# ATSAME51G19A_CAN_BREAKOUT.net
KiCad netlist of a schematic drawn in EAGLE
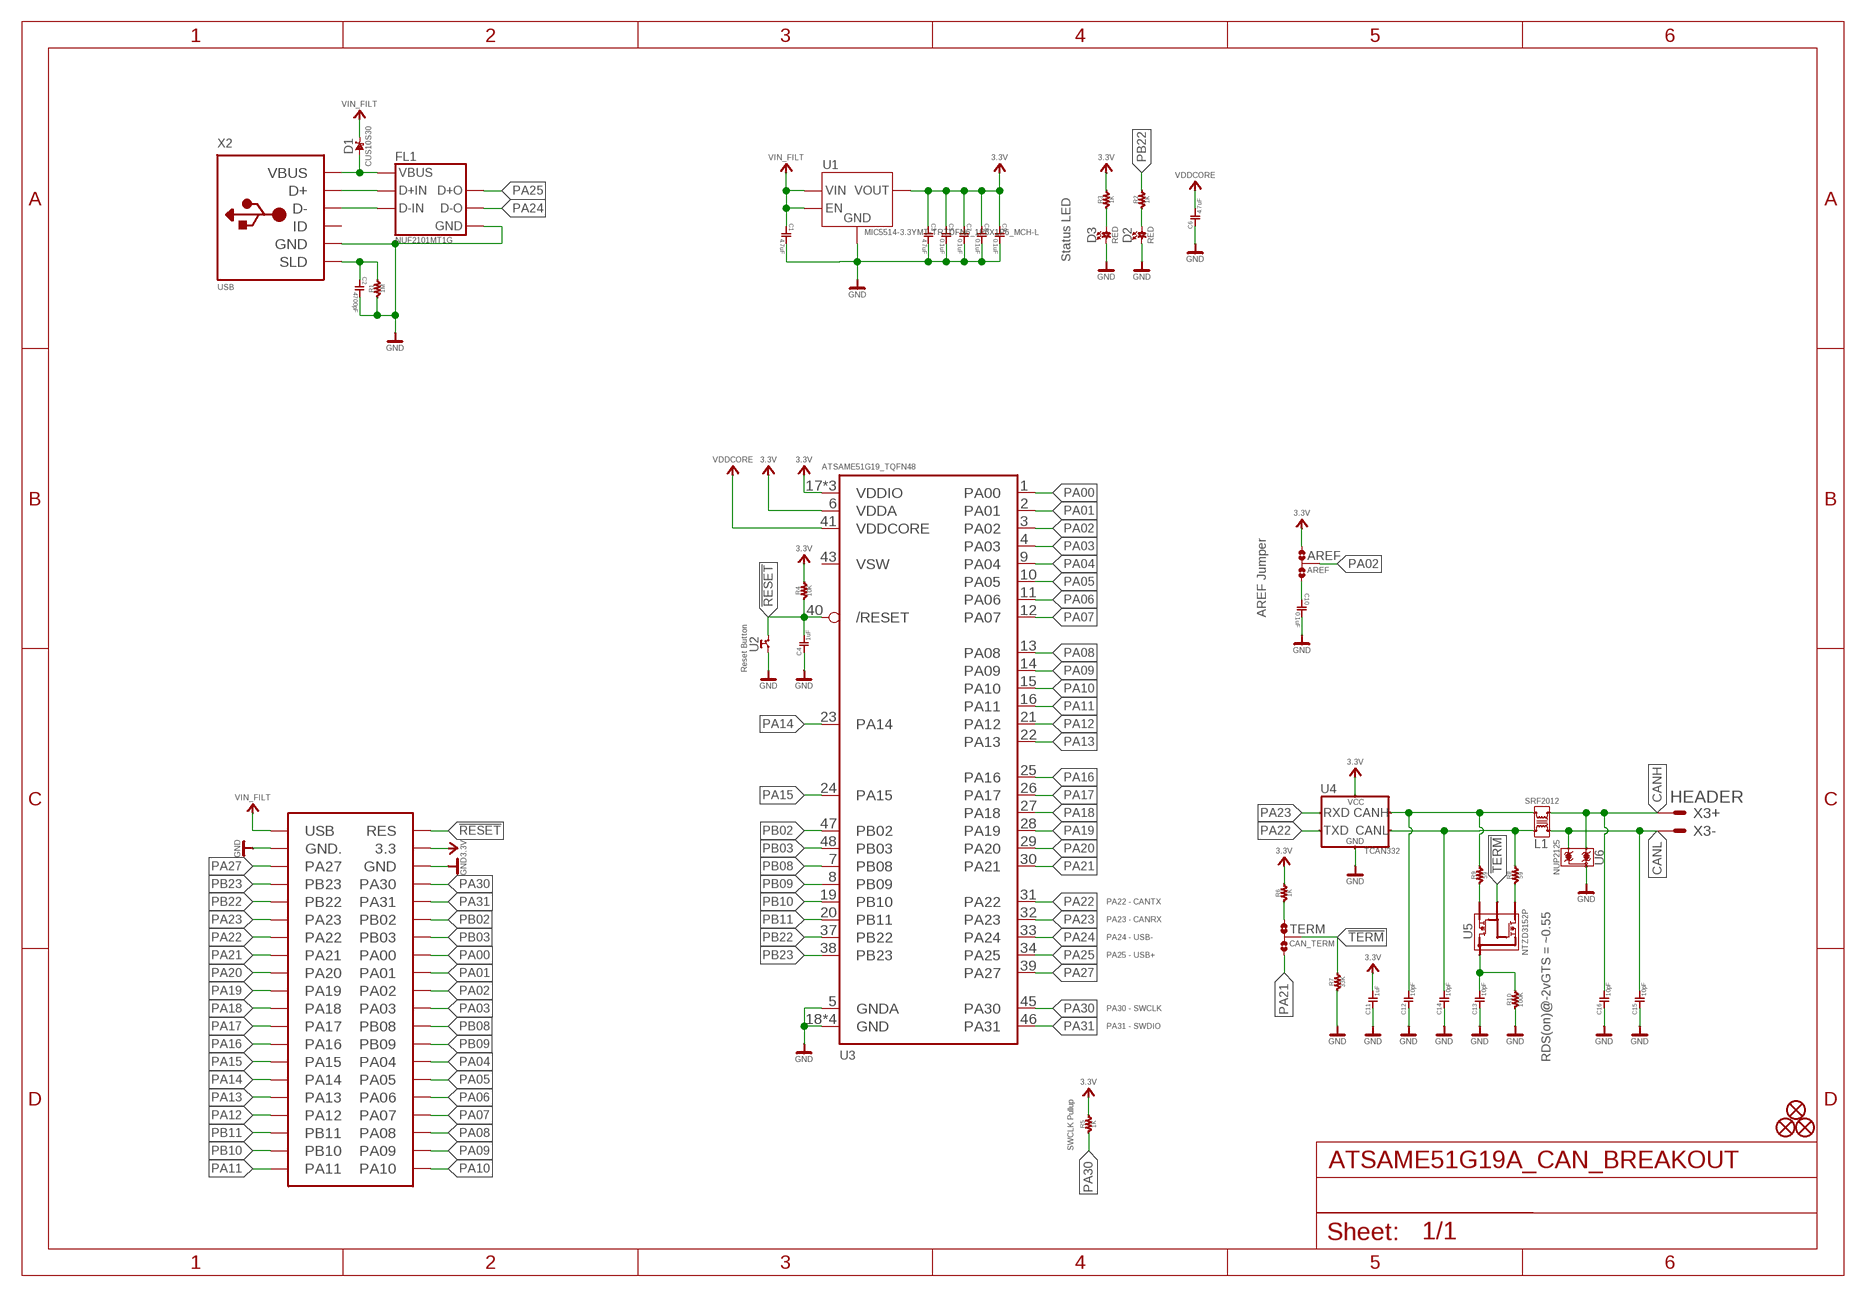
[diagram p0: schematic, sheet 1, part 1 of 2]
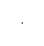
[diagram p1: schematic, sheet 1, part 2 of 2]

(export (version "E")
  (design (tool "Eeschema 10.0.6"))
  (components
    (comp (ref "AREF")
      (value "AREF")
      (footprint "eagle-import:C0R-JMP")
      (libsource (lib "eagle-import") (part "0R-JUMPC"))
    )
    (comp (ref "C1")
      (value "4.7uF")
      (footprint "eagle-import:CAP0402")
      (fields (field (name "MPN") "CL05A106MP8NUB8") (field (name "VOLTAGE") "10V"))
      (libsource (lib "eagle-import") (part "CAPACITOR0402"))
    )
    (comp (ref "C2")
      (value "4700pF")
      (footprint "eagle-import:CAP0402")
      (fields (field (name "MPN") "CC0402KRX7R8BB472") (field (name "VOLTAGE") "25V"))
      (libsource (lib "eagle-import") (part "CAPACITOR0402"))
    )
    (comp (ref "C3")
      (value "4.7uF")
      (footprint "eagle-import:CAP0402")
      (fields (field (name "MPN") "GRM155R60J106ME05D") (field (name "VOLTAGE") "6.3V"))
      (libsource (lib "eagle-import") (part "CAPACITOR0402"))
    )
    (comp (ref "C4")
      (value "1uF")
      (footprint "eagle-import:CAP0402")
      (fields (field (name "MPN") "CL05A105KQ5NNNC") (field (name "VOLTAGE") "6.3V"))
      (libsource (lib "eagle-import") (part "CAPACITOR0402"))
    )
    (comp (ref "C5")
      (value "0.1uF")
      (footprint "eagle-import:CAP0402")
      (fields (field (name "MPN") "CL05A105KQ5NNNC") (field (name "VOLTAGE") "6.3V"))
      (libsource (lib "eagle-import") (part "CAPACITOR0402"))
    )
    (comp (ref "C6")
      (value "4.7uF")
      (footprint "eagle-import:CAP0402")
      (fields (field (name "MPN") "GRM155R60J106ME05D") (field (name "VOLTAGE") "6.3V"))
      (libsource (lib "eagle-import") (part "CAPACITOR0402"))
    )
    (comp (ref "C7")
      (value "0.1uF")
      (footprint "eagle-import:CAP0402")
      (fields (field (name "MPN") "CL05A105KQ5NNNC") (field (name "VOLTAGE") "6.3V"))
      (libsource (lib "eagle-import") (part "CAPACITOR0402"))
    )
    (comp (ref "C8")
      (value "0.1uF")
      (footprint "eagle-import:CAP0402")
      (fields (field (name "MPN") "CL05A105KQ5NNNC") (field (name "VOLTAGE") "6.3V"))
      (libsource (lib "eagle-import") (part "CAPACITOR0402"))
    )
    (comp (ref "C9")
      (value "0.1uF")
      (footprint "eagle-import:CAP0402")
      (fields (field (name "MPN") "CL05A105KQ5NNNC") (field (name "VOLTAGE") "6.3V"))
      (libsource (lib "eagle-import") (part "CAPACITOR0402"))
    )
    (comp (ref "C10")
      (value "0.1uF")
      (footprint "eagle-import:CAP0402")
      (fields (field (name "MPN") "CL05A105KQ5NNNC") (field (name "VOLTAGE") "6.3V"))
      (libsource (lib "eagle-import") (part "CAPACITOR0402"))
    )
    (comp (ref "C11")
      (value "1uF")
      (footprint "eagle-import:CAP0402")
      (fields (field (name "MPN") "CL05A105KQ5NNNC") (field (name "VOLTAGE") "6.3V"))
      (libsource (lib "eagle-import") (part "CAPACITOR0402"))
    )
    (comp (ref "C12")
      (value "10pF")
      (footprint "eagle-import:CAP0402")
      (fields (field (name "MPN") "C0402C100K5RAC7867") (field (name "VOLTAGE") "50V"))
      (libsource (lib "eagle-import") (part "CAPACITOR0402"))
    )
    (comp (ref "C13")
      (value "10pF")
      (footprint "eagle-import:CAP0402")
      (fields (field (name "MPN") "C0402C100K5RAC7867") (field (name "VOLTAGE") "50V"))
      (libsource (lib "eagle-import") (part "CAPACITOR0402"))
    )
    (comp (ref "C14")
      (value "10pF")
      (footprint "eagle-import:CAP0402")
      (fields (field (name "MPN") "C0402C100K5RAC7867") (field (name "VOLTAGE") "50V"))
      (libsource (lib "eagle-import") (part "CAPACITOR0402"))
    )
    (comp (ref "C15")
      (value "10pF")
      (footprint "eagle-import:CAP0402")
      (fields (field (name "MPN") "C0402C100K5RAC7867") (field (name "VOLTAGE") "50V"))
      (libsource (lib "eagle-import") (part "CAPACITOR0402"))
    )
    (comp (ref "C16")
      (value "10pF")
      (footprint "eagle-import:CAP0402")
      (fields (field (name "MPN") "C0402C100K5RAC7867") (field (name "VOLTAGE") "50V"))
      (libsource (lib "eagle-import") (part "CAPACITOR0402"))
    )
    (comp (ref "D1")
      (value "CUS10S30")
      (footprint "eagle-import:X3-WLB1608-2")
      (fields (field (name "MPN") "SDM2U30CSP-7"))
      (libsource (lib "eagle-import") (part "SCHOTTKYX3-WLB1608-2"))
    )
    (comp (ref "D2")
      (value "0603 LED")
      (footprint "eagle-import:LED-0603")
      (fields (field (name "COLOR") "RED") (field (name "MPN") "LNJ8W0C83RA"))
      (libsource (lib "eagle-import") (part "LED-SMD0603"))
    )
    (comp (ref "D3")
      (value "0603 LED")
      (footprint "eagle-import:LED-0603")
      (fields (field (name "COLOR") "RED") (field (name "MPN") "LNJ8W0C83RA"))
      (libsource (lib "eagle-import") (part "LED-SMD0603"))
    )
    (comp (ref "FID1")
      (value "MICROBUILDER_FIDUCIAL_0.5MM")
      (footprint "eagle-import:MICROBUILDER_FIDUCIAL_0.5MM")
      (libsource (lib "eagle-import") (part "MICROBUILDER_FIDUCIAL_0.5MM"))
    )
    (comp (ref "FID2")
      (value "MICROBUILDER_FIDUCIAL_0.5MM")
      (footprint "eagle-import:MICROBUILDER_FIDUCIAL_0.5MM")
      (libsource (lib "eagle-import") (part "MICROBUILDER_FIDUCIAL_0.5MM"))
    )
    (comp (ref "FID3")
      (value "MICROBUILDER_FIDUCIAL_0.5MM")
      (footprint "eagle-import:MICROBUILDER_FIDUCIAL_0.5MM")
      (libsource (lib "eagle-import") (part "MICROBUILDER_FIDUCIAL_0.5MM"))
    )
    (comp (ref "FL1")
      (value "NUF2101MT1G")
      (footprint "eagle-import:SOT95P275X110-6N")
      (fields (field (name "MOUSER_PART_NUMBER") "863-NUF2101MT1G"))
      (libsource (lib "eagle-import") (part "NUF2101MT1G"))
    )
    (comp (ref "L1")
      (value "SRF2012")
      (footprint "eagle-import:SRF2012AA")
      (fields (field (name "MPN") "SRF2012-121YA"))
      (libsource (lib "eagle-import") (part "SRF2012AA"))
    )
    (comp (ref "R1")
      (value "1M")
      (footprint "eagle-import:RES0402")
      (fields
        (field (name "MPN") "PFR05S-105-FNH")
        (field (name "TOLERANCE") "1%")
        (field (name "WATTAGE") "1/16W")
      )
      (libsource (lib "eagle-import") (part "RESISTOR0402"))
    )
    (comp (ref "R2")
      (value "1K")
      (footprint "eagle-import:RES0402")
      (fields
        (field (name "MPN") "CR0402-FX-1002GLF")
        (field (name "TOLERANCE") "1%")
        (field (name "WATTAGE") "1/16W")
      )
      (libsource (lib "eagle-import") (part "RESISTOR0402"))
    )
    (comp (ref "R3")
      (value "1K")
      (footprint "eagle-import:RES0402")
      (fields
        (field (name "MPN") "CR0402-FX-1002GLF")
        (field (name "TOLERANCE") "1%")
        (field (name "WATTAGE") "1/16W")
      )
      (libsource (lib "eagle-import") (part "RESISTOR0402"))
    )
    (comp (ref "R4")
      (value "10K")
      (footprint "eagle-import:RES0402")
      (fields
        (field (name "MPN") "CR0402-FX-1002GLF")
        (field (name "TOLERANCE") "1%")
        (field (name "WATTAGE") "1/16W")
      )
      (libsource (lib "eagle-import") (part "RESISTOR0402"))
    )
    (comp (ref "R5")
      (value "1K")
      (footprint "eagle-import:RES0402")
      (fields
        (field (name "MPN") "PFR05S-102-FNH")
        (field (name "TOLERANCE") "1%")
        (field (name "WATTAGE") "1/16W")
      )
      (libsource (lib "eagle-import") (part "RESISTOR0402"))
    )
    (comp (ref "R6")
      (value "1K")
      (footprint "eagle-import:RES0402")
      (fields
        (field (name "MPN") "PFR05S-102-FNH")
        (field (name "TOLERANCE") "1%")
        (field (name "WATTAGE") "1/16W")
      )
      (libsource (lib "eagle-import") (part "RESISTOR0402"))
    )
    (comp (ref "R7")
      (value "33K")
      (footprint "eagle-import:RES0402")
      (fields
        (field (name "MPN") "RMCF0402FT33K0")
        (field (name "TOLERANCE") "1%")
        (field (name "WATTAGE") "1/16W")
      )
      (libsource (lib "eagle-import") (part "RESISTOR0402"))
    )
    (comp (ref "R8")
      (value "59")
      (footprint "eagle-import:RES0603")
      (fields
        (field (name "MPN") "CRCW060359R0FKEAHP")
        (field (name "TOLERANCE") "1%")
        (field (name "WATTAGE") "1/3W")
      )
      (libsource (lib "eagle-import") (part "RESISTOR0603"))
    )
    (comp (ref "R9")
      (value "59")
      (footprint "eagle-import:RES0603")
      (fields
        (field (name "MPN") "CRCW060359R0FKEAHP")
        (field (name "TOLERANCE") "1%")
        (field (name "WATTAGE") "1/3W")
      )
      (libsource (lib "eagle-import") (part "RESISTOR0603"))
    )
    (comp (ref "R10")
      (value "100K")
      (footprint "eagle-import:RES0402")
      (fields
        (field (name "MPN") "CR0402-FX-1003GLF")
        (field (name "TOLERANCE") "1%")
        (field (name "WATTAGE") "1/16W")
      )
      (libsource (lib "eagle-import") (part "RESISTOR0402"))
    )
    (comp (ref "TERM")
      (value "CAN_TERM")
      (footprint "eagle-import:C0R-JMP")
      (libsource (lib "eagle-import") (part "0R-JUMPC"))
    )
    (comp (ref "U1")
      (value "MIC5514-3.3YMT-TRTDFN6_1P6X1P6_MCH-L")
      (footprint "eagle-import:TDFN6_1P6X1P6_MCH-L")
      (fields
        (field (name "MANUFACTURER_PART_NUMBER") "MIC5514-3.3YMT-TR")
        (field (name "COPYRIGHT") "Copyright (C) 2018 Accelerated Designs. All rights reserved")
      )
      (libsource (lib "eagle-import") (part "MIC5514-3.3YMT-TRTDFN6_1P6X1P6_MCH-L"))
    )
    (comp (ref "U2")
      (value "PUSH_SWITCHPTS815")
      (footprint "eagle-import:SWITCH_PTS815")
      (fields (field (name "MPN") "PTS815 SJM 250 SMTR LFS"))
      (libsource (lib "eagle-import") (part "PUSH_SWITCHPTS815"))
    )
    (comp (ref "U3")
      (value "ATSAME51G19_TQFN48")
      (footprint "eagle-import:TQFN48_7MM")
      (fields (field (name "MPN") "ATSAME51G19A-MF"))
      (libsource (lib "eagle-import") (part "ATSAME51G19_TQFN48"))
    )
    (comp (ref "U4")
      (value "TCAN332")
      (footprint "eagle-import:DCN0008A")
      (fields (field (name "MPN") "TCAN332DCNR"))
      (libsource (lib "eagle-import") (part "TCAN332"))
    )
    (comp (ref "U5")
      (value "NTZD3152P")
      (footprint "eagle-import:SOT-563")
      (fields (field (name "MPN") "NTZD3152PT1G"))
      (libsource (lib "eagle-import") (part "PMOS_ARRAY_CANTNTZD3152P"))
    )
    (comp (ref "U6")
      (value "NUP2125")
      (footprint "eagle-import:SC70")
      (fields (field (name "MPN") "NUP2125WTT1G"))
      (libsource (lib "eagle-import") (part "NUP2125"))
    )
    (comp (ref "X1")
      (value "CONN")
      (footprint "eagle-import:BOARDOUTLINE")
      (libsource (lib "eagle-import") (part "SAME-BOARD"))
    )
    (comp (ref "X2")
      (value "USB")
      (footprint "eagle-import:10118194")
      (fields (field (name "MPN") "10118194-0001LF"))
      (libsource (lib "eagle-import") (part "USB"))
    )
    (comp (ref "X3")
      (value "HEADER")
      (footprint "eagle-import:22-23-2021")
      (fields (field (name "MF") "MOLEX") (field (name "MPN") "22-23-2021"))
      (libsource (lib "eagle-import") (part "22-23-2021"))
    )
  )
  (nets
    (net (code "1") (name "/~{RESET}") (class "Default")
      (node (ref "C4") (pin "2") (pinfunction "C2_2") (pintype "passive"))
      (node (ref "R4") (pin "1") (pinfunction "P$1_1") (pintype "passive"))
      (node (ref "U2") (pin "P$3") (pinfunction "2_P$3") (pintype "passive"))
      (node (ref "U2") (pin "P$4") (pinfunction "2_P$4") (pintype "passive"))
      (node (ref "U3") (pin "40") (pinfunction "/RESET_40") (pintype "bidirectional"))
      (node (ref "X1") (pin "!RES") (pinfunction "RES_!RES") (pintype "bidirectional"))
    )
    (net (code "2") (name "/~{TERM}") (class "Default")
      (node (ref "R7") (pin "2") (pinfunction "P$2_2") (pintype "passive"))
      (node (ref "TERM") (pin "2") (pinfunction "2_2") (pintype "passive"))
      (node (ref "U5") (pin "P$2") (pinfunction "GATE_P$2") (pintype "passive"))
      (node (ref "U5") (pin "P$5") (pinfunction "GATE_P$5") (pintype "passive"))
    )
    (net (code "3") (name "3.3V") (class "Default")
      (node (ref "AREF") (pin "1") (pinfunction "1_1") (pintype "passive"))
      (node (ref "C11") (pin "2") (pinfunction "C2_2") (pintype "passive"))
      (node (ref "C3") (pin "1") (pinfunction "C1_1") (pintype "passive"))
      (node (ref "C5") (pin "1") (pinfunction "C1_1") (pintype "passive"))
      (node (ref "C7") (pin "1") (pinfunction "C1_1") (pintype "passive"))
      (node (ref "C8") (pin "1") (pinfunction "C1_1") (pintype "passive"))
      (node (ref "C9") (pin "1") (pinfunction "C1_1") (pintype "passive"))
      (node (ref "R3") (pin "2") (pinfunction "P$2_2") (pintype "passive"))
      (node (ref "R4") (pin "2") (pinfunction "P$2_2") (pintype "passive"))
      (node (ref "R5") (pin "2") (pinfunction "P$2_2") (pintype "passive"))
      (node (ref "R6") (pin "2") (pinfunction "P$2_2") (pintype "passive"))
      (node (ref "U1") (pin "4") (pinfunction "VOUT_4") (pintype "passive"))
      (node (ref "U1") (pin "5") (pinfunction "VOUT_5") (pintype "passive"))
      (node (ref "U3") (pin "17") (pinfunction "VDDIO_17") (pintype "passive"))
      (node (ref "U3") (pin "36") (pinfunction "VDDIO_36") (pintype "passive"))
      (node (ref "U3") (pin "44") (pinfunction "VDDIO_44") (pintype "passive"))
      (node (ref "U3") (pin "6") (pinfunction "VDDA_6") (pintype "passive"))
      (node (ref "U4") (pin "3") (pinfunction "VCC_3") (pintype "passive"))
      (node (ref "X1") (pin "3.3") (pinfunction "3.3_3.3") (pintype "bidirectional"))
    )
    (net (code "4") (name "CANH") (class "Default")
      (node (ref "C16") (pin "2") (pinfunction "C2_2") (pintype "passive"))
      (node (ref "L1") (pin "4") (pinfunction "4_4") (pintype "passive"))
      (node (ref "U6") (pin "1") (pinfunction "1_1") (pintype "passive"))
      (node (ref "X3") (pin "1") (pinfunction "S_1") (pintype "passive"))
    )
    (net (code "5") (name "CANL") (class "Default")
      (node (ref "C15") (pin "2") (pinfunction "C2_2") (pintype "passive"))
      (node (ref "L1") (pin "1") (pinfunction "1_1") (pintype "passive"))
      (node (ref "U6") (pin "2") (pinfunction "2_2") (pintype "passive"))
      (node (ref "X3") (pin "2") (pinfunction "S_2") (pintype "passive"))
    )
    (net (code "6") (name "GND") (class "Default")
      (node (ref "C1") (pin "2") (pinfunction "C2_2") (pintype "passive"))
      (node (ref "C10") (pin "2") (pinfunction "C2_2") (pintype "passive"))
      (node (ref "C11") (pin "1") (pinfunction "C1_1") (pintype "passive"))
      (node (ref "C12") (pin "1") (pinfunction "C1_1") (pintype "passive"))
      (node (ref "C13") (pin "1") (pinfunction "C1_1") (pintype "passive"))
      (node (ref "C14") (pin "1") (pinfunction "C1_1") (pintype "passive"))
      (node (ref "C15") (pin "1") (pinfunction "C1_1") (pintype "passive"))
      (node (ref "C16") (pin "1") (pinfunction "C1_1") (pintype "passive"))
      (node (ref "C2") (pin "2") (pinfunction "C2_2") (pintype "passive"))
      (node (ref "C3") (pin "2") (pinfunction "C2_2") (pintype "passive"))
      (node (ref "C4") (pin "1") (pinfunction "C1_1") (pintype "passive"))
      (node (ref "C5") (pin "2") (pinfunction "C2_2") (pintype "passive"))
      (node (ref "C6") (pin "1") (pinfunction "C1_1") (pintype "passive"))
      (node (ref "C7") (pin "2") (pinfunction "C2_2") (pintype "passive"))
      (node (ref "C8") (pin "2") (pinfunction "C2_2") (pintype "passive"))
      (node (ref "C9") (pin "2") (pinfunction "C2_2") (pintype "passive"))
      (node (ref "D2") (pin "C") (pinfunction "C_C") (pintype "passive"))
      (node (ref "D3") (pin "C") (pinfunction "C_C") (pintype "passive"))
      (node (ref "FL1") (pin "2") (pinfunction "GND_2") (pintype "power_in"))
      (node (ref "R1") (pin "1") (pinfunction "P$1_1") (pintype "passive"))
      (node (ref "R10") (pin "1") (pinfunction "P$1_1") (pintype "passive"))
      (node (ref "R7") (pin "1") (pinfunction "P$1_1") (pintype "passive"))
      (node (ref "U1") (pin "6") (pinfunction "GND_6") (pintype "power_in"))
      (node (ref "U1") (pin "7") (pinfunction "GND_7") (pintype "power_in"))
      (node (ref "U2") (pin "P$1") (pinfunction "1_P$1") (pintype "passive"))
      (node (ref "U2") (pin "P$2") (pinfunction "1_P$2") (pintype "passive"))
      (node (ref "U3") (pin "18") (pinfunction "GND_18") (pintype "passive"))
      (node (ref "U3") (pin "35") (pinfunction "GND_35") (pintype "passive"))
      (node (ref "U3") (pin "42") (pinfunction "GND_42") (pintype "passive"))
      (node (ref "U3") (pin "5") (pinfunction "GNDA_5") (pintype "passive"))
      (node (ref "U3") (pin "THERMAL") (pinfunction "GND_THERMAL") (pintype "passive"))
      (node (ref "U4") (pin "2") (pinfunction "GND_2") (pintype "power_in"))
      (node (ref "U6") (pin "3") (pinfunction "3_3") (pintype "passive"))
      (node (ref "X1") (pin "GND") (pinfunction "GND_GND") (pintype "bidirectional"))
      (node (ref "X1") (pin "GND.") (pinfunction "GND._GND.") (pintype "bidirectional"))
      (node (ref "X2") (pin "5") (pinfunction "GND_5") (pintype "power_in"))
    )
    (net (code "7") (name "Net-(C2-C1)") (class "Default")
      (node (ref "C2") (pin "1") (pinfunction "C1_1") (pintype "passive"))
      (node (ref "R1") (pin "2") (pinfunction "P$2_2") (pintype "passive"))
      (node (ref "X2") (pin "GND4") (pinfunction "SLD_GND4") (pintype "bidirectional"))
      (node (ref "X2") (pin "GND5") (pinfunction "SLD_GND5") (pintype "bidirectional"))
      (node (ref "X2") (pin "P$1") (pinfunction "SLD_P$1") (pintype "bidirectional"))
      (node (ref "X2") (pin "P$2") (pinfunction "SLD_P$2") (pintype "bidirectional"))
      (node (ref "X2") (pin "P$3") (pinfunction "SLD_P$3") (pintype "bidirectional"))
      (node (ref "X2") (pin "P$4") (pinfunction "SLD_P$4") (pintype "bidirectional"))
    )
    (net (code "8") (name "Net-(C10-C1)") (class "Default")
      (node (ref "AREF") (pin "3") (pinfunction "3_3") (pintype "passive"))
      (node (ref "C10") (pin "1") (pinfunction "C1_1") (pintype "passive"))
    )
    (net (code "9") (name "Net-(C12-C2)") (class "Default")
      (node (ref "C12") (pin "2") (pinfunction "C2_2") (pintype "passive"))
      (node (ref "L1") (pin "3") (pinfunction "3_3") (pintype "passive"))
      (node (ref "R9") (pin "2") (pinfunction "P$2_2") (pintype "passive"))
      (node (ref "U4") (pin "7") (pinfunction "CANH_7") (pintype "bidirectional"))
    )
    (net (code "10") (name "Net-(C13-C2)") (class "Default")
      (node (ref "C13") (pin "2") (pinfunction "C2_2") (pintype "passive"))
      (node (ref "R10") (pin "2") (pinfunction "P$2_2") (pintype "passive"))
      (node (ref "U5") (pin "P$4") (pinfunction "DRAIN1_P$4") (pintype "passive"))
      (node (ref "U5") (pin "P$6") (pinfunction "DRAIN1_P$6") (pintype "passive"))
    )
    (net (code "11") (name "Net-(C14-C2)") (class "Default")
      (node (ref "C14") (pin "2") (pinfunction "C2_2") (pintype "passive"))
      (node (ref "L1") (pin "2") (pinfunction "2_2") (pintype "passive"))
      (node (ref "R8") (pin "2") (pinfunction "P$2_2") (pintype "passive"))
      (node (ref "U4") (pin "6") (pinfunction "CANL_6") (pintype "bidirectional"))
    )
    (net (code "12") (name "Net-(FL1-D+I)") (class "Default")
      (node (ref "FL1") (pin "6") (pinfunction "D+I_6") (pintype "input"))
      (node (ref "X2") (pin "3") (pinfunction "D+_3") (pintype "bidirectional"))
    )
    (net (code "13") (name "Net-(FL1-D-_I)") (class "Default")
      (node (ref "FL1") (pin "4") (pinfunction "D-_I_4") (pintype "input"))
      (node (ref "X2") (pin "2") (pinfunction "D-_2") (pintype "bidirectional"))
    )
    (net (code "14") (name "Net-(FL1-VBUS)") (class "Default")
      (node (ref "D1") (pin "ANNODE") (pinfunction "ANNODE_ANNODE") (pintype "bidirectional"))
      (node (ref "FL1") (pin "5") (pinfunction "VBUS_5") (pintype "power_in"))
      (node (ref "X2") (pin "1") (pinfunction "VBUS_1") (pintype "output"))
    )
    (net (code "15") (name "Net-(R2-P$1)") (class "Default")
      (node (ref "D2") (pin "A") (pinfunction "A_A") (pintype "passive"))
      (node (ref "R2") (pin "1") (pinfunction "P$1_1") (pintype "passive"))
    )
    (net (code "16") (name "Net-(R3-P$1)") (class "Default")
      (node (ref "D3") (pin "A") (pinfunction "A_A") (pintype "passive"))
      (node (ref "R3") (pin "1") (pinfunction "P$1_1") (pintype "passive"))
    )
    (net (code "17") (name "Net-(R6-P$1)") (class "Default")
      (node (ref "R6") (pin "1") (pinfunction "P$1_1") (pintype "passive"))
      (node (ref "TERM") (pin "1") (pinfunction "1_1") (pintype "passive"))
    )
    (net (code "18") (name "Net-(R8-P$1)") (class "Default")
      (node (ref "R8") (pin "1") (pinfunction "P$1_1") (pintype "passive"))
      (node (ref "U5") (pin "P$3") (pinfunction "DRAIN2_P$3") (pintype "passive"))
    )
    (net (code "19") (name "Net-(R9-P$1)") (class "Default")
      (node (ref "R9") (pin "1") (pinfunction "P$1_1") (pintype "passive"))
      (node (ref "U5") (pin "P$1") (pinfunction "SOURCE1_P$1") (pintype "passive"))
    )
    (net (code "20") (name "PA00") (class "Default")
      (node (ref "U3") (pin "1") (pinfunction "PA00_1") (pintype "bidirectional"))
      (node (ref "X1") (pin "PA00") (pinfunction "PA00_PA00") (pintype "bidirectional"))
    )
    (net (code "21") (name "PA01") (class "Default")
      (node (ref "U3") (pin "2") (pinfunction "PA01_2") (pintype "bidirectional"))
      (node (ref "X1") (pin "PA01") (pinfunction "PA01_PA01") (pintype "bidirectional"))
    )
    (net (code "22") (name "PA02") (class "Default")
      (node (ref "AREF") (pin "2") (pinfunction "2_2") (pintype "passive"))
      (node (ref "U3") (pin "3") (pinfunction "PA02_3") (pintype "bidirectional"))
      (node (ref "X1") (pin "PA02") (pinfunction "PA02_PA02") (pintype "bidirectional"))
    )
    (net (code "23") (name "PA03") (class "Default")
      (node (ref "U3") (pin "4") (pinfunction "PA03_4") (pintype "bidirectional"))
      (node (ref "X1") (pin "PA03") (pinfunction "PA03_PA03") (pintype "bidirectional"))
    )
    (net (code "24") (name "PA04") (class "Default")
      (node (ref "U3") (pin "9") (pinfunction "PA04_9") (pintype "bidirectional"))
      (node (ref "X1") (pin "PA04") (pinfunction "PA04_PA04") (pintype "bidirectional"))
    )
    (net (code "25") (name "PA05") (class "Default")
      (node (ref "U3") (pin "10") (pinfunction "PA05_10") (pintype "bidirectional"))
      (node (ref "X1") (pin "PA05") (pinfunction "PA05_PA05") (pintype "bidirectional"))
    )
    (net (code "26") (name "PA06") (class "Default")
      (node (ref "U3") (pin "11") (pinfunction "PA06_11") (pintype "bidirectional"))
      (node (ref "X1") (pin "PA06") (pinfunction "PA06_PA06") (pintype "bidirectional"))
    )
    (net (code "27") (name "PA07") (class "Default")
      (node (ref "U3") (pin "12") (pinfunction "PA07_12") (pintype "bidirectional"))
      (node (ref "X1") (pin "PA07") (pinfunction "PA07_PA07") (pintype "bidirectional"))
    )
    (net (code "28") (name "PA08") (class "Default")
      (node (ref "U3") (pin "13") (pinfunction "PA08_13") (pintype "bidirectional"))
      (node (ref "X1") (pin "PA08") (pinfunction "PA08_PA08") (pintype "bidirectional"))
    )
    (net (code "29") (name "PA09") (class "Default")
      (node (ref "U3") (pin "14") (pinfunction "PA09_14") (pintype "bidirectional"))
      (node (ref "X1") (pin "PA09") (pinfunction "PA09_PA09") (pintype "bidirectional"))
    )
    (net (code "30") (name "PA10") (class "Default")
      (node (ref "U3") (pin "15") (pinfunction "PA10_15") (pintype "bidirectional"))
      (node (ref "X1") (pin "PA10") (pinfunction "PA10_PA10") (pintype "bidirectional"))
    )
    (net (code "31") (name "PA11") (class "Default")
      (node (ref "U3") (pin "16") (pinfunction "PA11_16") (pintype "bidirectional"))
      (node (ref "X1") (pin "PA11") (pinfunction "PA11_PA11") (pintype "bidirectional"))
    )
    (net (code "32") (name "PA12") (class "Default")
      (node (ref "U3") (pin "21") (pinfunction "PA12_21") (pintype "bidirectional"))
      (node (ref "X1") (pin "PA12") (pinfunction "PA12_PA12") (pintype "bidirectional"))
    )
    (net (code "33") (name "PA13") (class "Default")
      (node (ref "U3") (pin "22") (pinfunction "PA13_22") (pintype "bidirectional"))
      (node (ref "X1") (pin "PA13") (pinfunction "PA13_PA13") (pintype "bidirectional"))
    )
    (net (code "34") (name "PA14") (class "Default")
      (node (ref "U3") (pin "23") (pinfunction "PA14_23") (pintype "bidirectional"))
      (node (ref "X1") (pin "PA14") (pinfunction "PA14_PA14") (pintype "bidirectional"))
    )
    (net (code "35") (name "PA15") (class "Default")
      (node (ref "U3") (pin "24") (pinfunction "PA15_24") (pintype "bidirectional"))
      (node (ref "X1") (pin "PA15") (pinfunction "PA15_PA15") (pintype "bidirectional"))
    )
    (net (code "36") (name "PA16") (class "Default")
      (node (ref "U3") (pin "25") (pinfunction "PA16_25") (pintype "bidirectional"))
      (node (ref "X1") (pin "PA16") (pinfunction "PA16_PA16") (pintype "bidirectional"))
    )
    (net (code "37") (name "PA17") (class "Default")
      (node (ref "U3") (pin "26") (pinfunction "PA17_26") (pintype "bidirectional"))
      (node (ref "X1") (pin "PA17") (pinfunction "PA17_PA17") (pintype "bidirectional"))
    )
    (net (code "38") (name "PA18") (class "Default")
      (node (ref "U3") (pin "27") (pinfunction "PA18_27") (pintype "bidirectional"))
      (node (ref "X1") (pin "PA18") (pinfunction "PA18_PA18") (pintype "bidirectional"))
    )
    (net (code "39") (name "PA19") (class "Default")
      (node (ref "U3") (pin "28") (pinfunction "PA19_28") (pintype "bidirectional"))
      (node (ref "X1") (pin "PA19") (pinfunction "PA19_PA19") (pintype "bidirectional"))
    )
    (net (code "40") (name "PA20") (class "Default")
      (node (ref "U3") (pin "29") (pinfunction "PA20_29") (pintype "bidirectional"))
      (node (ref "X1") (pin "PA20") (pinfunction "PA20_PA20") (pintype "bidirectional"))
    )
    (net (code "41") (name "PA21") (class "Default")
      (node (ref "TERM") (pin "3") (pinfunction "3_3") (pintype "passive"))
      (node (ref "U3") (pin "30") (pinfunction "PA21_30") (pintype "bidirectional"))
      (node (ref "X1") (pin "PA21") (pinfunction "PA21_PA21") (pintype "bidirectional"))
    )
    (net (code "42") (name "PA22") (class "Default")
      (node (ref "U3") (pin "31") (pinfunction "PA22_31") (pintype "bidirectional"))
      (node (ref "U4") (pin "1") (pinfunction "TXD_1") (pintype "input"))
      (node (ref "X1") (pin "PA22") (pinfunction "PA22_PA22") (pintype "bidirectional"))
    )
    (net (code "43") (name "PA23") (class "Default")
      (node (ref "U3") (pin "32") (pinfunction "PA23_32") (pintype "bidirectional"))
      (node (ref "U4") (pin "4") (pinfunction "RXD_4") (pintype "output"))
      (node (ref "X1") (pin "PA23") (pinfunction "PA23_PA23") (pintype "bidirectional"))
    )
    (net (code "44") (name "PA24") (class "Default")
      (node (ref "FL1") (pin "3") (pinfunction "D-_O_3") (pintype "output"))
      (node (ref "U3") (pin "33") (pinfunction "PA24_33") (pintype "bidirectional"))
    )
    (net (code "45") (name "PA25") (class "Default")
      (node (ref "FL1") (pin "1") (pinfunction "D+_O_1") (pintype "output"))
      (node (ref "U3") (pin "34") (pinfunction "PA25_34") (pintype "bidirectional"))
    )
    (net (code "46") (name "PA27") (class "Default")
      (node (ref "U3") (pin "39") (pinfunction "PA27_39") (pintype "bidirectional"))
      (node (ref "X1") (pin "PA27") (pinfunction "PA27_PA27") (pintype "bidirectional"))
    )
    (net (code "47") (name "PA30") (class "Default")
      (node (ref "R5") (pin "1") (pinfunction "P$1_1") (pintype "passive"))
      (node (ref "U3") (pin "45") (pinfunction "PA30_45") (pintype "bidirectional"))
      (node (ref "X1") (pin "PA30") (pinfunction "PA30_PA30") (pintype "bidirectional"))
    )
    (net (code "48") (name "PA31") (class "Default")
      (node (ref "U3") (pin "46") (pinfunction "PA31_46") (pintype "bidirectional"))
      (node (ref "X1") (pin "PA31") (pinfunction "PA31_PA31") (pintype "bidirectional"))
    )
    (net (code "49") (name "PB02") (class "Default")
      (node (ref "U3") (pin "47") (pinfunction "PB02_47") (pintype "bidirectional"))
      (node (ref "X1") (pin "PB02") (pinfunction "PB02_PB02") (pintype "bidirectional"))
    )
    (net (code "50") (name "PB03") (class "Default")
      (node (ref "U3") (pin "48") (pinfunction "PB03_48") (pintype "bidirectional"))
      (node (ref "X1") (pin "PB03") (pinfunction "PB03_PB03") (pintype "bidirectional"))
    )
    (net (code "51") (name "PB08") (class "Default")
      (node (ref "U3") (pin "7") (pinfunction "PB08_7") (pintype "bidirectional"))
      (node (ref "X1") (pin "PB08") (pinfunction "PB08_PB08") (pintype "bidirectional"))
    )
    (net (code "52") (name "PB09") (class "Default")
      (node (ref "U3") (pin "8") (pinfunction "PB09_8") (pintype "bidirectional"))
      (node (ref "X1") (pin "PB09") (pinfunction "PB09_PB09") (pintype "bidirectional"))
    )
    (net (code "53") (name "PB10") (class "Default")
      (node (ref "U3") (pin "19") (pinfunction "PB10_19") (pintype "bidirectional"))
      (node (ref "X1") (pin "PB10") (pinfunction "PB10_PB10") (pintype "bidirectional"))
    )
    (net (code "54") (name "PB11") (class "Default")
      (node (ref "U3") (pin "20") (pinfunction "PB11_20") (pintype "bidirectional"))
      (node (ref "X1") (pin "PB11") (pinfunction "PB11_PB11") (pintype "bidirectional"))
    )
    (net (code "55") (name "PB22") (class "Default")
      (node (ref "R2") (pin "2") (pinfunction "P$2_2") (pintype "passive"))
      (node (ref "U3") (pin "37") (pinfunction "PB22_37") (pintype "bidirectional"))
      (node (ref "X1") (pin "PB22") (pinfunction "PB22_PB22") (pintype "bidirectional"))
    )
    (net (code "56") (name "PB23") (class "Default")
      (node (ref "U3") (pin "38") (pinfunction "PB23_38") (pintype "bidirectional"))
      (node (ref "X1") (pin "PB23") (pinfunction "PB23_PB23") (pintype "bidirectional"))
    )
    (net (code "57") (name "VDDCORE") (class "Default")
      (node (ref "C6") (pin "2") (pinfunction "C2_2") (pintype "passive"))
      (node (ref "U3") (pin "41") (pinfunction "VDDCORE_41") (pintype "passive"))
    )
    (net (code "58") (name "VIN_FILT") (class "Default")
      (node (ref "C1") (pin "1") (pinfunction "C1_1") (pintype "passive"))
      (node (ref "D1") (pin "CATHODE") (pinfunction "CATHODE_CATHODE") (pintype "bidirectional"))
      (node (ref "U1") (pin "1") (pinfunction "EN_1") (pintype "input"))
      (node (ref "U1") (pin "2") (pinfunction "EN_2") (pintype "input"))
      (node (ref "U1") (pin "3") (pinfunction "VIN_3") (pintype "input"))
      (node (ref "X1") (pin "USB") (pinfunction "USB_USB") (pintype "bidirectional"))
    )
    (net (code "59") (name "unconnected-(U3-VSW-Pad43)") (class "Default")
      (node (ref "U3") (pin "43") (pinfunction "VSW_43") (pintype "passive"))
    )
    (net (code "60") (name "unconnected-(X2-ID-Pad4)") (class "Default")
      (node (ref "X2") (pin "4") (pinfunction "ID_4") (pintype "bidirectional"))
    )
  )
)
